# strain-gauge-amplifier.net
KiCad netlist of a schematic drawn in EAGLE
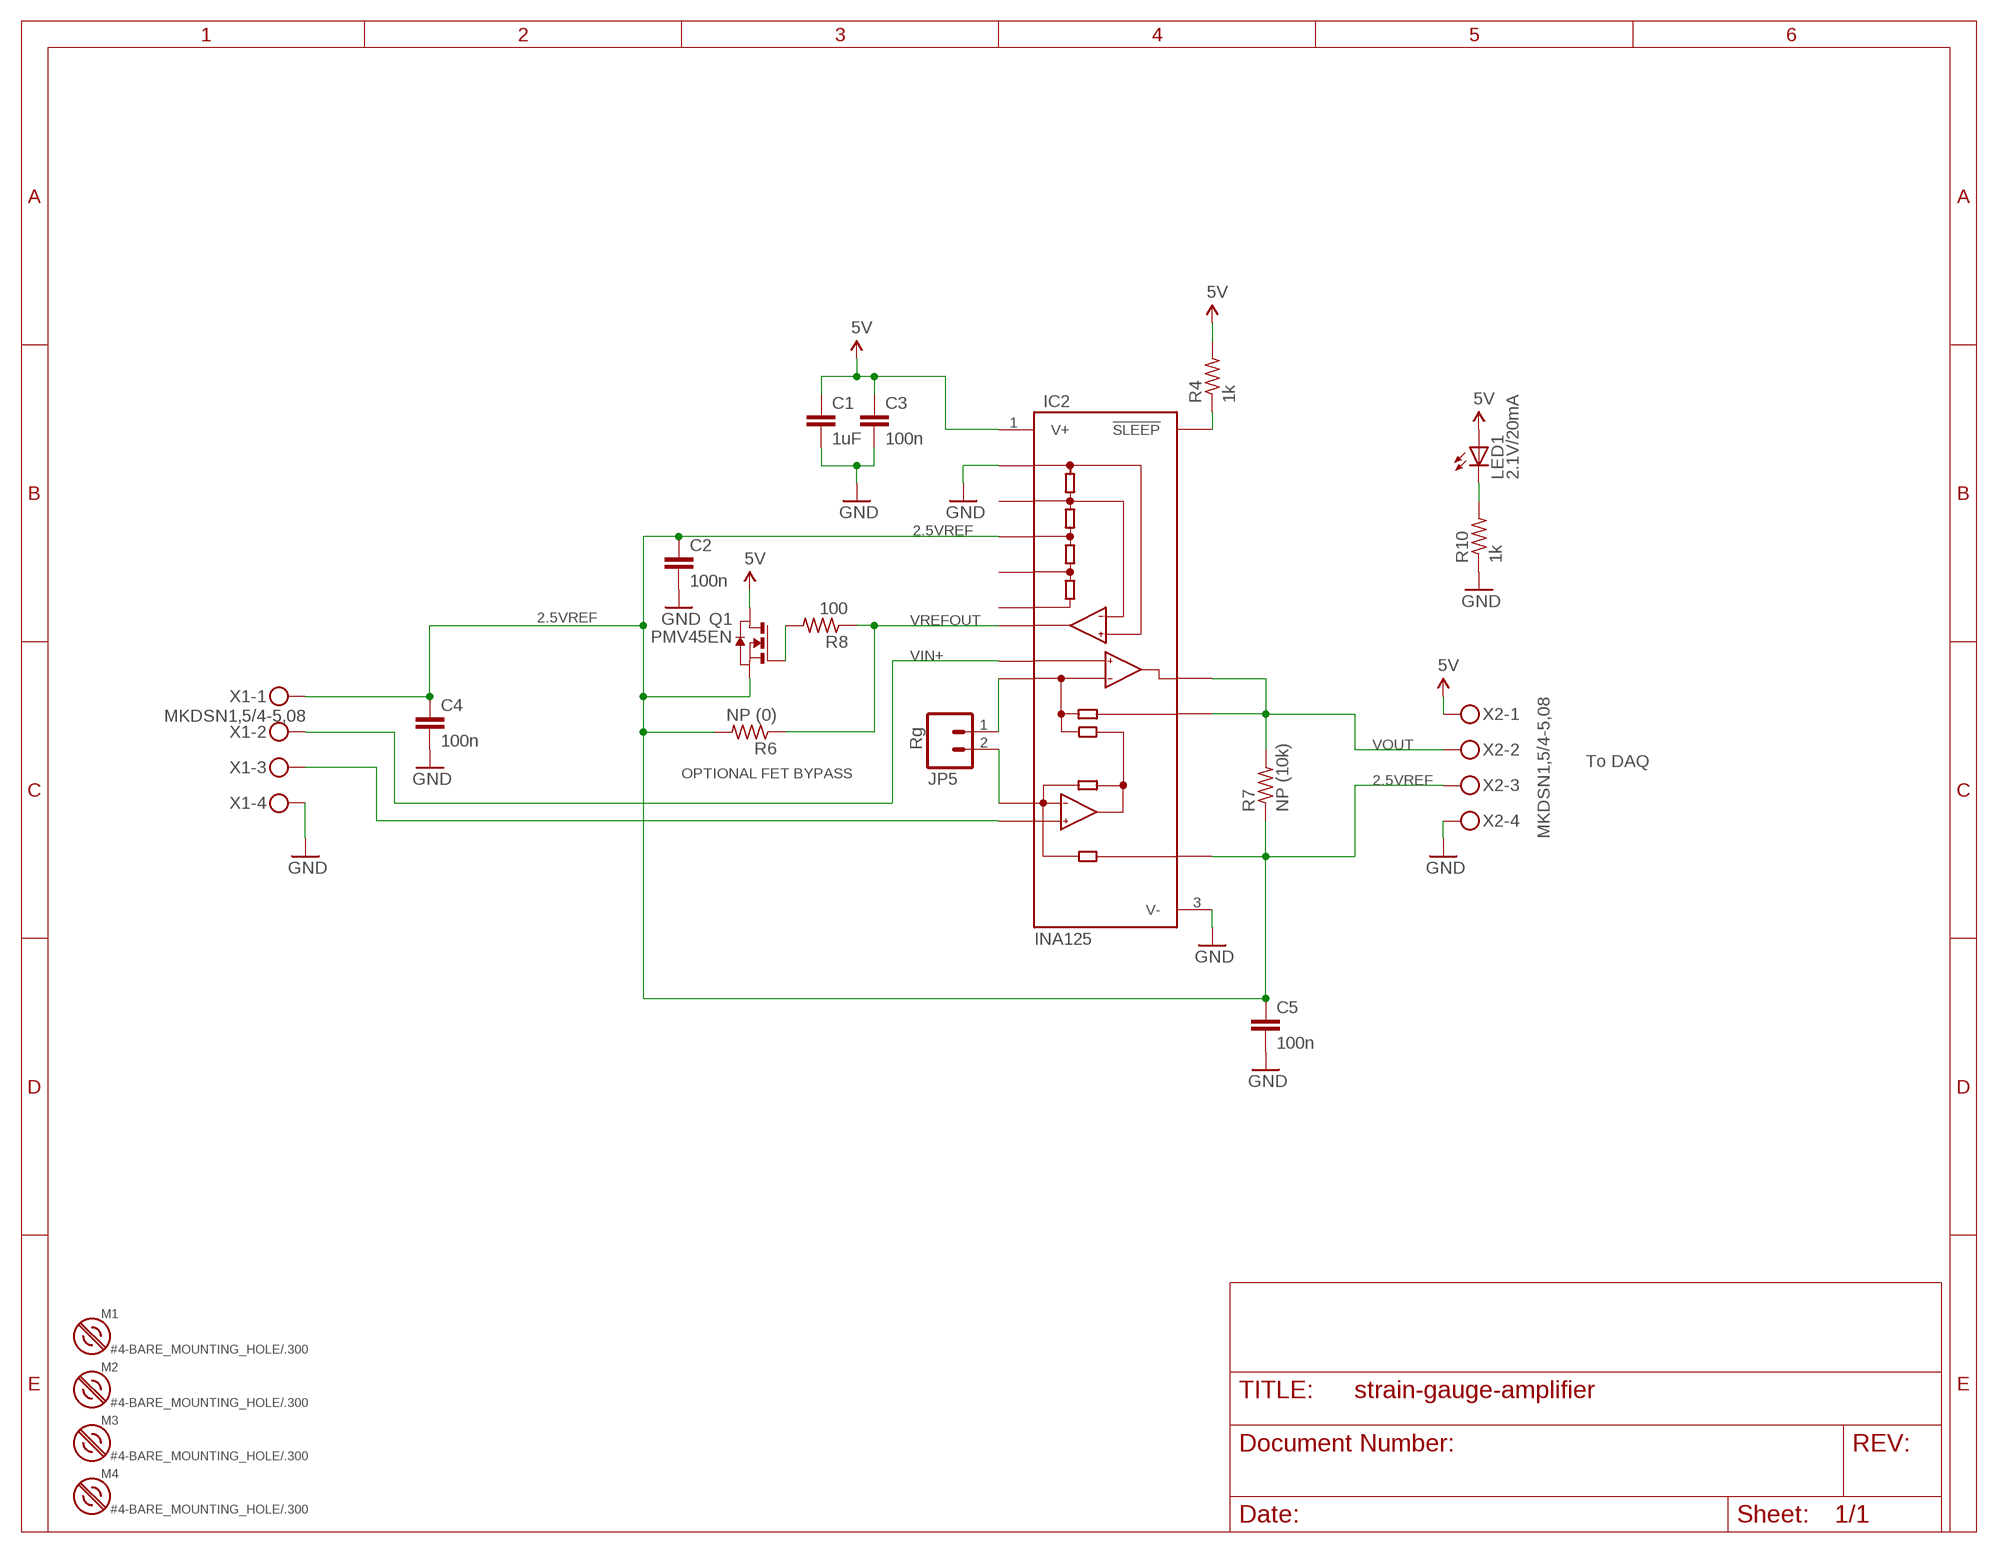
[diagram p0: schematic, sheet 1]

(export (version "E")
  (design (tool "Eeschema 10.0.6"))
  (components
    (comp (ref "C1")
      (value "1uF")
      (footprint "eagle-import:0805-C-NOSILK")
      (libsource (lib "eagle-import") (part "C-EU0805-C-NOSILK"))
    )
    (comp (ref "C2")
      (value "100n")
      (footprint "eagle-import:0805-C-NOSILK")
      (libsource (lib "eagle-import") (part "C-EU0805-C-NOSILK"))
    )
    (comp (ref "C3")
      (value "100n")
      (footprint "eagle-import:0805-C-NOSILK")
      (libsource (lib "eagle-import") (part "C-EU0805-C-NOSILK"))
    )
    (comp (ref "C4")
      (value "100n")
      (footprint "eagle-import:0805-C-NOSILK")
      (libsource (lib "eagle-import") (part "C-EU0805-C-NOSILK"))
    )
    (comp (ref "C5")
      (value "100n")
      (footprint "eagle-import:0805-C-NOSILK")
      (libsource (lib "eagle-import") (part "C-EU0805-C-NOSILK"))
    )
    (comp (ref "IC2")
      (value "INA125")
      (footprint "eagle-import:SO16")
      (libsource (lib "eagle-import") (part "INA125"))
    )
    (comp (ref "JP5")
      (value "Rg")
      (footprint "eagle-import:SCREWTERMINAL-5MM-2")
      (libsource (lib "eagle-import") (part "M025MM"))
    )
    (comp (ref "LED1")
      (value "2.1V/20mA")
      (footprint "eagle-import:LED-0603")
      (libsource (lib "eagle-import") (part "LED0603"))
    )
    (comp (ref "M1")
      (value "#4-BARE_MOUNTING_HOLE/.300")
      (footprint "eagle-import:#4_.300-BARE+STD_NUT_OR_STAR_WASHER")
      (libsource (lib "eagle-import") (part "#4-BARE_MOUNTING_HOLE/.300"))
    )
    (comp (ref "M2")
      (value "#4-BARE_MOUNTING_HOLE/.300")
      (footprint "eagle-import:#4_.300-BARE+STD_NUT_OR_STAR_WASHER")
      (libsource (lib "eagle-import") (part "#4-BARE_MOUNTING_HOLE/.300"))
    )
    (comp (ref "M3")
      (value "#4-BARE_MOUNTING_HOLE/.300")
      (footprint "eagle-import:#4_.300-BARE+STD_NUT_OR_STAR_WASHER")
      (libsource (lib "eagle-import") (part "#4-BARE_MOUNTING_HOLE/.300"))
    )
    (comp (ref "M4")
      (value "#4-BARE_MOUNTING_HOLE/.300")
      (footprint "eagle-import:#4_.300-BARE+STD_NUT_OR_STAR_WASHER")
      (libsource (lib "eagle-import") (part "#4-BARE_MOUNTING_HOLE/.300"))
    )
    (comp (ref "Q1")
      (value "PMV45EN")
      (footprint "eagle-import:SOT23")
      (libsource (lib "eagle-import") (part "PMV45EN"))
    )
    (comp (ref "R4")
      (value "1k")
      (footprint "eagle-import:0805-C-NOSILK")
      (libsource (lib "eagle-import") (part "R-US_0805-C-NOSILK"))
    )
    (comp (ref "R6")
      (value "NP (0)")
      (footprint "eagle-import:0805-C-NOSILK")
      (libsource (lib "eagle-import") (part "R-US_0805-C-NOSILK"))
    )
    (comp (ref "R7")
      (value "NP (10k)")
      (footprint "eagle-import:0805-C-NOSILK")
      (libsource (lib "eagle-import") (part "R-US_0805-C-NOSILK"))
    )
    (comp (ref "R8")
      (value "100")
      (footprint "eagle-import:0805-C-NOSILK")
      (libsource (lib "eagle-import") (part "R-US_0805-C-NOSILK"))
    )
    (comp (ref "R10")
      (value "1k")
      (footprint "eagle-import:0805-C-NOSILK")
      (libsource (lib "eagle-import") (part "R-US_0805-C-NOSILK"))
    )
    (comp (ref "X1")
      (value "MKDSN1,5/4-5,08")
      (footprint "eagle-import:MKDSN1,5_4-5,08")
      (libsource (lib "eagle-import") (part "MKDSN1,5/4-5,08"))
    )
    (comp (ref "X2")
      (value "MKDSN1,5/4-5,08")
      (footprint "eagle-import:MKDSN1,5_4-5,08")
      (libsource (lib "eagle-import") (part "MKDSN1,5/4-5,08"))
    )
  )
  (nets
    (net (code "1") (name "/2.5VREF") (class "Default")
      (node (ref "C2") (pin "1") (pinfunction "1_1") (pintype "passive"))
      (node (ref "C4") (pin "1") (pinfunction "1_1") (pintype "passive"))
      (node (ref "C5") (pin "1") (pinfunction "1_1") (pintype "passive"))
      (node (ref "IC2") (pin "14") (pinfunction "REF2.5_14") (pintype "output"))
      (node (ref "IC2") (pin "5") (pinfunction "REF_5") (pintype "passive"))
      (node (ref "Q1") (pin "2") (pinfunction "S_2") (pintype "passive"))
      (node (ref "R6") (pin "2") (pinfunction "2_2") (pintype "passive"))
      (node (ref "R7") (pin "1") (pinfunction "1_1") (pintype "passive"))
      (node (ref "X1") (pin "1") (pinfunction "KL_1") (pintype "passive"))
      (node (ref "X2") (pin "3") (pinfunction "KL_3") (pintype "passive"))
    )
    (net (code "2") (name "/VIN+") (class "Default")
      (node (ref "IC2") (pin "6") (pinfunction "+IN_6") (pintype "input"))
      (node (ref "X1") (pin "2") (pinfunction "KL_2") (pintype "passive"))
    )
    (net (code "3") (name "/VOUT") (class "Default")
      (node (ref "IC2") (pin "10") (pinfunction "OUT_10") (pintype "output"))
      (node (ref "IC2") (pin "11") (pinfunction "SENSE_11") (pintype "passive"))
      (node (ref "R7") (pin "2") (pinfunction "2_2") (pintype "passive"))
      (node (ref "X2") (pin "2") (pinfunction "KL_2") (pintype "passive"))
    )
    (net (code "4") (name "/VREFOUT") (class "Default")
      (node (ref "IC2") (pin "4") (pinfunction "REFOUT_4") (pintype "output"))
      (node (ref "R6") (pin "1") (pinfunction "1_1") (pintype "passive"))
      (node (ref "R8") (pin "1") (pinfunction "1_1") (pintype "passive"))
    )
    (net (code "5") (name "5V") (class "Default")
      (node (ref "C1") (pin "1") (pinfunction "1_1") (pintype "passive"))
      (node (ref "C3") (pin "1") (pinfunction "1_1") (pintype "passive"))
      (node (ref "IC2") (pin "1") (pinfunction "V+_1") (pintype "power_in"))
      (node (ref "LED1") (pin "A") (pinfunction "A_A") (pintype "passive"))
      (node (ref "Q1") (pin "3") (pinfunction "D_3") (pintype "passive"))
      (node (ref "R4") (pin "2") (pinfunction "2_2") (pintype "passive"))
      (node (ref "X2") (pin "1") (pinfunction "KL_1") (pintype "passive"))
    )
    (net (code "6") (name "GND") (class "Default")
      (node (ref "C1") (pin "2") (pinfunction "2_2") (pintype "passive"))
      (node (ref "C2") (pin "2") (pinfunction "2_2") (pintype "passive"))
      (node (ref "C3") (pin "2") (pinfunction "2_2") (pintype "passive"))
      (node (ref "C4") (pin "2") (pinfunction "2_2") (pintype "passive"))
      (node (ref "C5") (pin "2") (pinfunction "2_2") (pintype "passive"))
      (node (ref "IC2") (pin "12") (pinfunction "REFCOM_12") (pintype "passive"))
      (node (ref "IC2") (pin "3") (pinfunction "V-_3") (pintype "power_in"))
      (node (ref "R10") (pin "1") (pinfunction "1_1") (pintype "passive"))
      (node (ref "X1") (pin "4") (pinfunction "KL_4") (pintype "passive"))
      (node (ref "X2") (pin "4") (pinfunction "KL_4") (pintype "passive"))
    )
    (net (code "7") (name "Net-(IC2--VIN)") (class "Default")
      (node (ref "IC2") (pin "7") (pinfunction "-VIN_7") (pintype "input"))
      (node (ref "X1") (pin "3") (pinfunction "KL_3") (pintype "passive"))
    )
    (net (code "8") (name "Net-(IC2-RG-Pad8)") (class "Default")
      (node (ref "IC2") (pin "8") (pinfunction "RG_8") (pintype "passive"))
      (node (ref "JP5") (pin "2") (pinfunction "2_2") (pintype "passive"))
    )
    (net (code "9") (name "Net-(IC2-RG-Pad9)") (class "Default")
      (node (ref "IC2") (pin "9") (pinfunction "RG_9") (pintype "passive"))
      (node (ref "JP5") (pin "1") (pinfunction "1_1") (pintype "passive"))
    )
    (net (code "10") (name "Net-(IC2-~{SLEEP})") (class "Default")
      (node (ref "IC2") (pin "2") (pinfunction "~{SLEEP}_2") (pintype "input"))
      (node (ref "R4") (pin "1") (pinfunction "1_1") (pintype "passive"))
    )
    (net (code "11") (name "Net-(LED1-PadC)") (class "Default")
      (node (ref "LED1") (pin "C") (pinfunction "C_C") (pintype "passive"))
      (node (ref "R10") (pin "2") (pinfunction "2_2") (pintype "passive"))
    )
    (net (code "12") (name "Net-(Q1-G)") (class "Default")
      (node (ref "Q1") (pin "1") (pinfunction "G_1") (pintype "passive"))
      (node (ref "R8") (pin "2") (pinfunction "2_2") (pintype "passive"))
    )
    (net (code "13") (name "unconnected-(IC2-REF5-Pad15)") (class "Default")
      (node (ref "IC2") (pin "15") (pinfunction "REF5_15") (pintype "output"))
    )
    (net (code "14") (name "unconnected-(IC2-REF10-Pad16)") (class "Default")
      (node (ref "IC2") (pin "16") (pinfunction "REF10_16") (pintype "output"))
    )
    (net (code "15") (name "unconnected-(IC2-REFBG-Pad13)") (class "Default")
      (node (ref "IC2") (pin "13") (pinfunction "REFBG_13") (pintype "output"))
    )
  )
)
